# auxDaqUnit.net
KiCad netlist of a schematic drawn in EAGLE
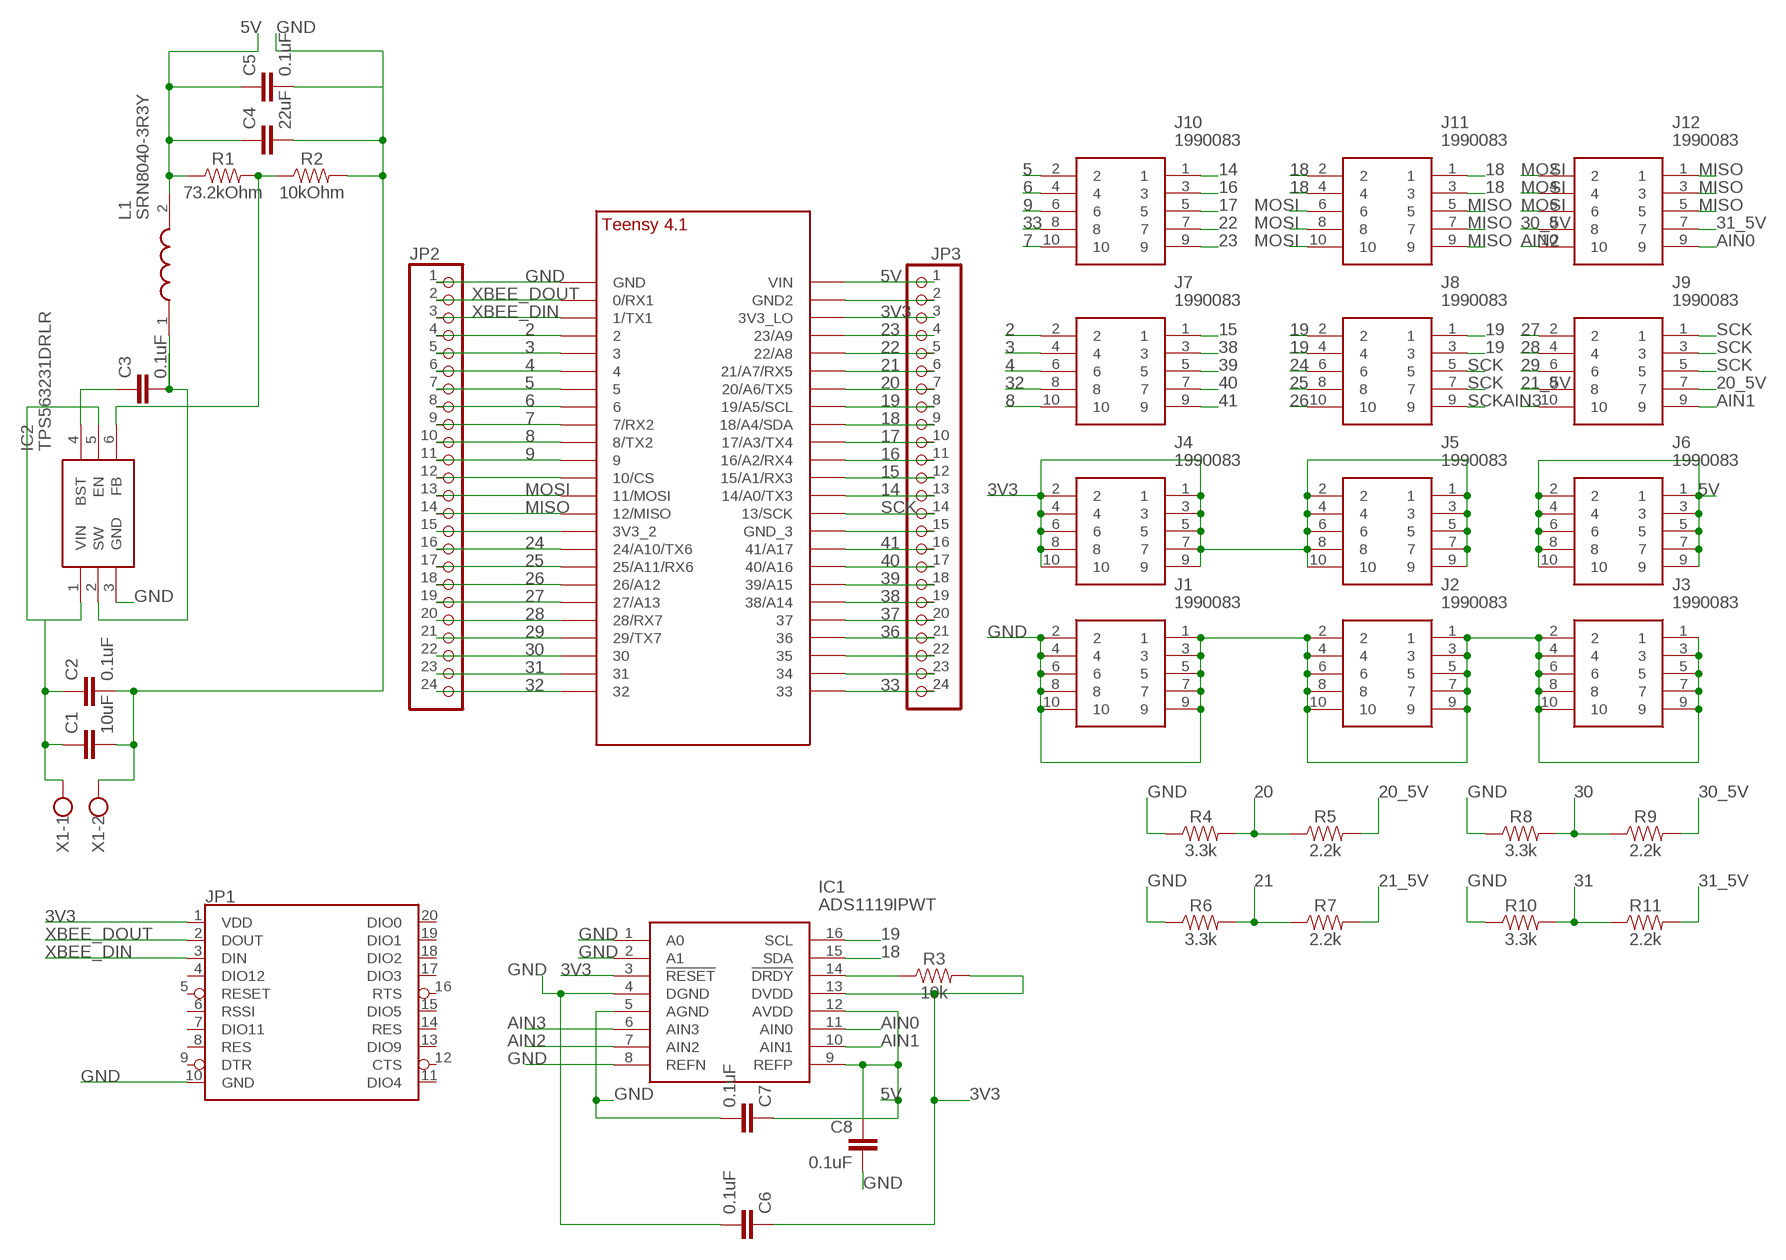
[diagram p0: schematic, sheet 1]

(export (version "E")
  (design (tool "Eeschema 10.0.6"))
  (components
    (comp (ref "C1")
      (value "10uF")
      (footprint "eagle-import:0603")
      (libsource (lib "eagle-import") (part "10UF-0603-6.3V-20%"))
    )
    (comp (ref "C2")
      (value "0.1uF")
      (footprint "eagle-import:0603")
      (libsource (lib "eagle-import") (part "0.1UF-0603-25V-(+80/-20%)"))
    )
    (comp (ref "C3")
      (value "0.1uF")
      (footprint "eagle-import:0603")
      (libsource (lib "eagle-import") (part "0.1UF-0603-25V-(+80/-20%)"))
    )
    (comp (ref "C4")
      (value "22uF")
      (footprint "eagle-import:0805")
      (libsource (lib "eagle-import") (part "22UF-0805-6.3V-20%"))
    )
    (comp (ref "C5")
      (value "0.1uF")
      (footprint "eagle-import:0603")
      (libsource (lib "eagle-import") (part "0.1UF-0603-25V-(+80/-20%)"))
    )
    (comp (ref "C6")
      (value "0.1uF")
      (footprint "eagle-import:0603")
      (libsource (lib "eagle-import") (part "0.1UF-0603-25V-(+80/-20%)"))
    )
    (comp (ref "C7")
      (value "0.1uF")
      (footprint "eagle-import:0603")
      (libsource (lib "eagle-import") (part "0.1UF-0603-25V-(+80/-20%)"))
    )
    (comp (ref "C8")
      (value "0.1uF")
      (footprint "eagle-import:0603")
      (libsource (lib "eagle-import") (part "0.1UF-0603-25V-(+80/-20%)"))
    )
    (comp (ref "IC1")
      (value "ADS1119IPWT")
      (footprint "eagle-import:SOP65P640X120-16N")
      (fields (field (name "MOUSER_PART_NUMBER") "595-ADS1119IPWT"))
      (libsource (lib "eagle-import") (part "ADS1119IPWT"))
    )
    (comp (ref "IC2")
      (value "TPS563231DRLR")
      (footprint "eagle-import:SOTFL50P160X60-6N")
      (fields (field (name "MOUSER_PART_NUMBER") "595-TPS563231DRLR"))
      (libsource (lib "eagle-import") (part "TPS563231DRLR"))
    )
    (comp (ref "J1")
      (value "1990083")
      (footprint "eagle-import:1990083")
      (fields (field (name "MOUSER_PART_NUMBER") "651-1990083"))
      (libsource (lib "eagle-import") (part "1990083"))
    )
    (comp (ref "J2")
      (value "1990083")
      (footprint "eagle-import:1990083")
      (fields (field (name "MOUSER_PART_NUMBER") "651-1990083"))
      (libsource (lib "eagle-import") (part "1990083"))
    )
    (comp (ref "J3")
      (value "1990083")
      (footprint "eagle-import:1990083")
      (fields (field (name "MOUSER_PART_NUMBER") "651-1990083"))
      (libsource (lib "eagle-import") (part "1990083"))
    )
    (comp (ref "J4")
      (value "1990083")
      (footprint "eagle-import:1990083")
      (fields (field (name "MOUSER_PART_NUMBER") "651-1990083"))
      (libsource (lib "eagle-import") (part "1990083"))
    )
    (comp (ref "J5")
      (value "1990083")
      (footprint "eagle-import:1990083")
      (fields (field (name "MOUSER_PART_NUMBER") "651-1990083"))
      (libsource (lib "eagle-import") (part "1990083"))
    )
    (comp (ref "J6")
      (value "1990083")
      (footprint "eagle-import:1990083")
      (fields (field (name "MOUSER_PART_NUMBER") "651-1990083"))
      (libsource (lib "eagle-import") (part "1990083"))
    )
    (comp (ref "J7")
      (value "1990083")
      (footprint "eagle-import:1990083")
      (fields (field (name "MOUSER_PART_NUMBER") "651-1990083"))
      (libsource (lib "eagle-import") (part "1990083"))
    )
    (comp (ref "J8")
      (value "1990083")
      (footprint "eagle-import:1990083")
      (fields (field (name "MOUSER_PART_NUMBER") "651-1990083"))
      (libsource (lib "eagle-import") (part "1990083"))
    )
    (comp (ref "J9")
      (value "1990083")
      (footprint "eagle-import:1990083")
      (fields (field (name "MOUSER_PART_NUMBER") "651-1990083"))
      (libsource (lib "eagle-import") (part "1990083"))
    )
    (comp (ref "J10")
      (value "1990083")
      (footprint "eagle-import:1990083")
      (fields (field (name "MOUSER_PART_NUMBER") "651-1990083"))
      (libsource (lib "eagle-import") (part "1990083"))
    )
    (comp (ref "J11")
      (value "1990083")
      (footprint "eagle-import:1990083")
      (fields (field (name "MOUSER_PART_NUMBER") "651-1990083"))
      (libsource (lib "eagle-import") (part "1990083"))
    )
    (comp (ref "J12")
      (value "1990083")
      (footprint "eagle-import:1990083")
      (fields (field (name "MOUSER_PART_NUMBER") "651-1990083"))
      (libsource (lib "eagle-import") (part "1990083"))
    )
    (comp (ref "JP1")
      (value "XBEE")
      (footprint "eagle-import:XBEE")
      (libsource (lib "eagle-import") (part "XBEE"))
    )
    (comp (ref "JP2")
      (value "PINHD-1X24")
      (footprint "eagle-import:1X24")
      (libsource (lib "eagle-import") (part "PINHD-1X24"))
    )
    (comp (ref "JP3")
      (value "PINHD-1X24")
      (footprint "eagle-import:1X24")
      (libsource (lib "eagle-import") (part "PINHD-1X24"))
    )
    (comp (ref "L1")
      (value "SRN8040-3R3Y")
      (footprint "eagle-import:SRN8040-3R3Y")
      (fields (field (name "MOUSER_PART_NUMBER") "652-SRN8040-3R3Y"))
      (libsource (lib "eagle-import") (part "SRN8040-3R3Y"))
    )
    (comp (ref "R1")
      (value "73.2kOhm")
      (footprint "eagle-import:0603")
      (libsource (lib "eagle-import") (part "RESISTOR0603"))
    )
    (comp (ref "R2")
      (value "10kOhm")
      (footprint "eagle-import:0603")
      (libsource (lib "eagle-import") (part "RESISTOR0603"))
    )
    (comp (ref "R3")
      (value "10k")
      (footprint "eagle-import:0603")
      (libsource (lib "eagle-import") (part "10KOHM-0603-1/10W-1%"))
    )
    (comp (ref "R4")
      (value "3.3k")
      (footprint "eagle-import:0603")
      (libsource (lib "eagle-import") (part "3.3KOHM-0603-1/10W-1%"))
    )
    (comp (ref "R5")
      (value "2.2k")
      (footprint "eagle-import:0603")
      (libsource (lib "eagle-import") (part "2.2KOHM-0603-1/10W-1%"))
    )
    (comp (ref "R6")
      (value "3.3k")
      (footprint "eagle-import:0603")
      (libsource (lib "eagle-import") (part "3.3KOHM-0603-1/10W-1%"))
    )
    (comp (ref "R7")
      (value "2.2k")
      (footprint "eagle-import:0603")
      (libsource (lib "eagle-import") (part "2.2KOHM-0603-1/10W-1%"))
    )
    (comp (ref "R8")
      (value "3.3k")
      (footprint "eagle-import:0603")
      (libsource (lib "eagle-import") (part "3.3KOHM-0603-1/10W-1%"))
    )
    (comp (ref "R9")
      (value "2.2k")
      (footprint "eagle-import:0603")
      (libsource (lib "eagle-import") (part "2.2KOHM-0603-1/10W-1%"))
    )
    (comp (ref "R10")
      (value "3.3k")
      (footprint "eagle-import:0603")
      (libsource (lib "eagle-import") (part "3.3KOHM-0603-1/10W-1%"))
    )
    (comp (ref "R11")
      (value "2.2k")
      (footprint "eagle-import:0603")
      (libsource (lib "eagle-import") (part "2.2KOHM-0603-1/10W-1%"))
    )
    (comp (ref "U$1")
      (value "TEENSY_4.1_SIMPLE")
      (footprint "eagle-import:TEENSY_4.1_SIMPLE")
      (libsource (lib "eagle-import") (part "TEENSY_4.1_SIMPLE"))
    )
    (comp (ref "X1")
      (value "W237-102")
      (footprint "eagle-import:W237-102")
      (fields (field (name "MPN") "237-102"))
      (libsource (lib "eagle-import") (part "W237-102"))
    )
  )
  (nets
    (net (code "1") (name "/2") (class "Default")
      (node (ref "J7") (pin "2") (pinfunction "2_2") (pintype "bidirectional"))
      (node (ref "JP2") (pin "4") (pinfunction "4_4") (pintype "passive"))
      (node (ref "U$1") (pin "2") (pinfunction "2_2") (pintype "bidirectional"))
    )
    (net (code "2") (name "/3") (class "Default")
      (node (ref "J7") (pin "4") (pinfunction "4_4") (pintype "bidirectional"))
      (node (ref "JP2") (pin "5") (pinfunction "5_5") (pintype "passive"))
      (node (ref "U$1") (pin "3/CANTX") (pinfunction "3_3/CANTX") (pintype "bidirectional"))
    )
    (net (code "3") (name "/3V3") (class "Default")
      (node (ref "C6") (pin "1") (pinfunction "1_1") (pintype "passive"))
      (node (ref "IC1") (pin "13") (pinfunction "DVDD_13") (pintype "bidirectional"))
      (node (ref "IC1") (pin "3") (pinfunction "~{RESET}_3") (pintype "bidirectional"))
      (node (ref "J4") (pin "1") (pinfunction "1_1") (pintype "bidirectional"))
      (node (ref "J4") (pin "10") (pinfunction "10_10") (pintype "bidirectional"))
      (node (ref "J4") (pin "2") (pinfunction "2_2") (pintype "bidirectional"))
      (node (ref "J4") (pin "3") (pinfunction "3_3") (pintype "bidirectional"))
      (node (ref "J4") (pin "4") (pinfunction "4_4") (pintype "bidirectional"))
      (node (ref "J4") (pin "5") (pinfunction "5_5") (pintype "bidirectional"))
      (node (ref "J4") (pin "6") (pinfunction "6_6") (pintype "bidirectional"))
      (node (ref "J4") (pin "7") (pinfunction "7_7") (pintype "bidirectional"))
      (node (ref "J4") (pin "8") (pinfunction "8_8") (pintype "bidirectional"))
      (node (ref "J4") (pin "9") (pinfunction "9_9") (pintype "bidirectional"))
      (node (ref "J5") (pin "1") (pinfunction "1_1") (pintype "bidirectional"))
      (node (ref "J5") (pin "10") (pinfunction "10_10") (pintype "bidirectional"))
      (node (ref "J5") (pin "2") (pinfunction "2_2") (pintype "bidirectional"))
      (node (ref "J5") (pin "3") (pinfunction "3_3") (pintype "bidirectional"))
      (node (ref "J5") (pin "4") (pinfunction "4_4") (pintype "bidirectional"))
      (node (ref "J5") (pin "5") (pinfunction "5_5") (pintype "bidirectional"))
      (node (ref "J5") (pin "6") (pinfunction "6_6") (pintype "bidirectional"))
      (node (ref "J5") (pin "7") (pinfunction "7_7") (pintype "bidirectional"))
      (node (ref "J5") (pin "8") (pinfunction "8_8") (pintype "bidirectional"))
      (node (ref "J5") (pin "9") (pinfunction "9_9") (pintype "bidirectional"))
      (node (ref "JP1") (pin "1") (pinfunction "VDD_1") (pintype "power_in"))
      (node (ref "JP3") (pin "3") (pinfunction "3_3") (pintype "passive"))
      (node (ref "R3") (pin "2") (pinfunction "2_2") (pintype "passive"))
      (node (ref "U$1") (pin "3V3_LO") (pinfunction "3V3_LO_3V3_LO") (pintype "bidirectional"))
    )
    (net (code "4") (name "/4") (class "Default")
      (node (ref "J7") (pin "6") (pinfunction "6_6") (pintype "bidirectional"))
      (node (ref "JP2") (pin "6") (pinfunction "6_6") (pintype "passive"))
      (node (ref "U$1") (pin "4/CANRX") (pinfunction "4_4/CANRX") (pintype "bidirectional"))
    )
    (net (code "5") (name "/5") (class "Default")
      (node (ref "J10") (pin "2") (pinfunction "2_2") (pintype "bidirectional"))
      (node (ref "JP2") (pin "7") (pinfunction "7_7") (pintype "passive"))
      (node (ref "U$1") (pin "5") (pinfunction "5_5") (pintype "bidirectional"))
    )
    (net (code "6") (name "/5V") (class "Default")
      (node (ref "C4") (pin "1") (pinfunction "1_1") (pintype "passive"))
      (node (ref "C5") (pin "1") (pinfunction "1_1") (pintype "passive"))
      (node (ref "C7") (pin "1") (pinfunction "1_1") (pintype "passive"))
      (node (ref "C8") (pin "1") (pinfunction "1_1") (pintype "passive"))
      (node (ref "IC1") (pin "12") (pinfunction "AVDD_12") (pintype "bidirectional"))
      (node (ref "IC1") (pin "9") (pinfunction "REFP_9") (pintype "bidirectional"))
      (node (ref "J6") (pin "1") (pinfunction "1_1") (pintype "bidirectional"))
      (node (ref "J6") (pin "10") (pinfunction "10_10") (pintype "bidirectional"))
      (node (ref "J6") (pin "2") (pinfunction "2_2") (pintype "bidirectional"))
      (node (ref "J6") (pin "3") (pinfunction "3_3") (pintype "bidirectional"))
      (node (ref "J6") (pin "4") (pinfunction "4_4") (pintype "bidirectional"))
      (node (ref "J6") (pin "5") (pinfunction "5_5") (pintype "bidirectional"))
      (node (ref "J6") (pin "6") (pinfunction "6_6") (pintype "bidirectional"))
      (node (ref "J6") (pin "7") (pinfunction "7_7") (pintype "bidirectional"))
      (node (ref "J6") (pin "8") (pinfunction "8_8") (pintype "bidirectional"))
      (node (ref "J6") (pin "9") (pinfunction "9_9") (pintype "bidirectional"))
      (node (ref "JP3") (pin "1") (pinfunction "1_1") (pintype "passive"))
      (node (ref "L1") (pin "2") (pinfunction "2_2") (pintype "bidirectional"))
      (node (ref "R1") (pin "1") (pinfunction "1_1") (pintype "passive"))
      (node (ref "U$1") (pin "VIN") (pinfunction "VIN_VIN") (pintype "bidirectional"))
    )
    (net (code "7") (name "/6") (class "Default")
      (node (ref "J10") (pin "4") (pinfunction "4_4") (pintype "bidirectional"))
      (node (ref "JP2") (pin "8") (pinfunction "8_8") (pintype "passive"))
      (node (ref "U$1") (pin "6") (pinfunction "6_6") (pintype "bidirectional"))
    )
    (net (code "8") (name "/7") (class "Default")
      (node (ref "J10") (pin "10") (pinfunction "10_10") (pintype "bidirectional"))
      (node (ref "JP2") (pin "9") (pinfunction "9_9") (pintype "passive"))
      (node (ref "U$1") (pin "7") (pinfunction "7/RX2_7") (pintype "bidirectional"))
    )
    (net (code "9") (name "/8") (class "Default")
      (node (ref "J7") (pin "10") (pinfunction "10_10") (pintype "bidirectional"))
      (node (ref "JP2") (pin "10") (pinfunction "10_10") (pintype "passive"))
      (node (ref "U$1") (pin "8") (pinfunction "8/TX2_8") (pintype "bidirectional"))
    )
    (net (code "10") (name "/9") (class "Default")
      (node (ref "J10") (pin "6") (pinfunction "6_6") (pintype "bidirectional"))
      (node (ref "JP2") (pin "11") (pinfunction "11_11") (pintype "passive"))
      (node (ref "U$1") (pin "9/CS") (pinfunction "9_9/CS") (pintype "bidirectional"))
    )
    (net (code "11") (name "/14") (class "Default")
      (node (ref "J10") (pin "1") (pinfunction "1_1") (pintype "bidirectional"))
      (node (ref "JP3") (pin "13") (pinfunction "13_13") (pintype "passive"))
      (node (ref "U$1") (pin "14/A0") (pinfunction "14/A0/TX3_14/A0") (pintype "bidirectional"))
    )
    (net (code "12") (name "/15") (class "Default")
      (node (ref "J7") (pin "1") (pinfunction "1_1") (pintype "bidirectional"))
      (node (ref "JP3") (pin "12") (pinfunction "12_12") (pintype "passive"))
      (node (ref "U$1") (pin "15/A1") (pinfunction "15/A1/RX3_15/A1") (pintype "bidirectional"))
    )
    (net (code "13") (name "/16") (class "Default")
      (node (ref "J10") (pin "3") (pinfunction "3_3") (pintype "bidirectional"))
      (node (ref "JP3") (pin "11") (pinfunction "11_11") (pintype "passive"))
      (node (ref "U$1") (pin "16/A2") (pinfunction "16/A2/RX4_16/A2") (pintype "bidirectional"))
    )
    (net (code "14") (name "/17") (class "Default")
      (node (ref "J10") (pin "5") (pinfunction "5_5") (pintype "bidirectional"))
      (node (ref "JP3") (pin "10") (pinfunction "10_10") (pintype "passive"))
      (node (ref "U$1") (pin "17/A3") (pinfunction "17/A3/TX4_17/A3") (pintype "bidirectional"))
    )
    (net (code "15") (name "/18") (class "Default")
      (node (ref "IC1") (pin "15") (pinfunction "SDA_15") (pintype "bidirectional"))
      (node (ref "J11") (pin "1") (pinfunction "1_1") (pintype "bidirectional"))
      (node (ref "J11") (pin "2") (pinfunction "2_2") (pintype "bidirectional"))
      (node (ref "J11") (pin "3") (pinfunction "3_3") (pintype "bidirectional"))
      (node (ref "J11") (pin "4") (pinfunction "4_4") (pintype "bidirectional"))
      (node (ref "JP3") (pin "9") (pinfunction "9_9") (pintype "passive"))
      (node (ref "U$1") (pin "18/A4/SDA") (pinfunction "18/A4/SDA_18/A4/SDA") (pintype "bidirectional"))
    )
    (net (code "16") (name "/19") (class "Default")
      (node (ref "IC1") (pin "16") (pinfunction "SCL_16") (pintype "bidirectional"))
      (node (ref "J8") (pin "1") (pinfunction "1_1") (pintype "bidirectional"))
      (node (ref "J8") (pin "2") (pinfunction "2_2") (pintype "bidirectional"))
      (node (ref "J8") (pin "3") (pinfunction "3_3") (pintype "bidirectional"))
      (node (ref "J8") (pin "4") (pinfunction "4_4") (pintype "bidirectional"))
      (node (ref "JP3") (pin "8") (pinfunction "8_8") (pintype "passive"))
      (node (ref "U$1") (pin "19/A5/SCL") (pinfunction "19/A5/SCL_19/A5/SCL") (pintype "bidirectional"))
    )
    (net (code "17") (name "/20") (class "Default")
      (node (ref "JP3") (pin "7") (pinfunction "7_7") (pintype "passive"))
      (node (ref "R4") (pin "2") (pinfunction "2_2") (pintype "passive"))
      (node (ref "R5") (pin "1") (pinfunction "1_1") (pintype "passive"))
      (node (ref "U$1") (pin "20/A6") (pinfunction "20/A6/TX5_20/A6") (pintype "bidirectional"))
    )
    (net (code "18") (name "/20_5V") (class "Default")
      (node (ref "J9") (pin "7") (pinfunction "7_7") (pintype "bidirectional"))
      (node (ref "R5") (pin "2") (pinfunction "2_2") (pintype "passive"))
    )
    (net (code "19") (name "/21") (class "Default")
      (node (ref "JP3") (pin "6") (pinfunction "6_6") (pintype "passive"))
      (node (ref "R6") (pin "2") (pinfunction "2_2") (pintype "passive"))
      (node (ref "R7") (pin "1") (pinfunction "1_1") (pintype "passive"))
      (node (ref "U$1") (pin "21/A7") (pinfunction "21/A7/RX5_21/A7") (pintype "bidirectional"))
    )
    (net (code "20") (name "/21_5V") (class "Default")
      (node (ref "J9") (pin "8") (pinfunction "8_8") (pintype "bidirectional"))
      (node (ref "R7") (pin "2") (pinfunction "2_2") (pintype "passive"))
    )
    (net (code "21") (name "/22") (class "Default")
      (node (ref "J10") (pin "7") (pinfunction "7_7") (pintype "bidirectional"))
      (node (ref "JP3") (pin "5") (pinfunction "5_5") (pintype "passive"))
      (node (ref "U$1") (pin "22/A8") (pinfunction "22/A8_22/A8") (pintype "bidirectional"))
    )
    (net (code "22") (name "/23") (class "Default")
      (node (ref "J10") (pin "9") (pinfunction "9_9") (pintype "bidirectional"))
      (node (ref "JP3") (pin "4") (pinfunction "4_4") (pintype "passive"))
      (node (ref "U$1") (pin "23/A9") (pinfunction "23/A9_23/A9") (pintype "bidirectional"))
    )
    (net (code "23") (name "/24") (class "Default")
      (node (ref "J8") (pin "6") (pinfunction "6_6") (pintype "bidirectional"))
      (node (ref "JP2") (pin "16") (pinfunction "16_16") (pintype "passive"))
      (node (ref "U$1") (pin "24/A10") (pinfunction "24/A10/TX6_24/A10") (pintype "bidirectional"))
    )
    (net (code "24") (name "/25") (class "Default")
      (node (ref "J8") (pin "8") (pinfunction "8_8") (pintype "bidirectional"))
      (node (ref "JP2") (pin "17") (pinfunction "17_17") (pintype "passive"))
      (node (ref "U$1") (pin "25/A11") (pinfunction "25/A11/RX6_25/A11") (pintype "bidirectional"))
    )
    (net (code "25") (name "/26") (class "Default")
      (node (ref "J8") (pin "10") (pinfunction "10_10") (pintype "bidirectional"))
      (node (ref "JP2") (pin "18") (pinfunction "18_18") (pintype "passive"))
      (node (ref "U$1") (pin "26/A12") (pinfunction "26/A12_26/A12") (pintype "bidirectional"))
    )
    (net (code "26") (name "/27") (class "Default")
      (node (ref "J9") (pin "2") (pinfunction "2_2") (pintype "bidirectional"))
      (node (ref "JP2") (pin "19") (pinfunction "19_19") (pintype "passive"))
      (node (ref "U$1") (pin "27/A13") (pinfunction "27/A13_27/A13") (pintype "bidirectional"))
    )
    (net (code "27") (name "/28") (class "Default")
      (node (ref "J9") (pin "4") (pinfunction "4_4") (pintype "bidirectional"))
      (node (ref "JP2") (pin "20") (pinfunction "20_20") (pintype "passive"))
      (node (ref "U$1") (pin "28") (pinfunction "28/RX7_28") (pintype "bidirectional"))
    )
    (net (code "28") (name "/29") (class "Default")
      (node (ref "J9") (pin "6") (pinfunction "6_6") (pintype "bidirectional"))
      (node (ref "JP2") (pin "21") (pinfunction "21_21") (pintype "passive"))
      (node (ref "U$1") (pin "29") (pinfunction "29/TX7_29") (pintype "bidirectional"))
    )
    (net (code "29") (name "/30") (class "Default")
      (node (ref "JP2") (pin "22") (pinfunction "22_22") (pintype "passive"))
      (node (ref "R8") (pin "2") (pinfunction "2_2") (pintype "passive"))
      (node (ref "R9") (pin "1") (pinfunction "1_1") (pintype "passive"))
      (node (ref "U$1") (pin "30") (pinfunction "30_30") (pintype "bidirectional"))
    )
    (net (code "30") (name "/30_5V") (class "Default")
      (node (ref "J12") (pin "8") (pinfunction "8_8") (pintype "bidirectional"))
      (node (ref "R9") (pin "2") (pinfunction "2_2") (pintype "passive"))
    )
    (net (code "31") (name "/31") (class "Default")
      (node (ref "JP2") (pin "23") (pinfunction "23_23") (pintype "passive"))
      (node (ref "R10") (pin "2") (pinfunction "2_2") (pintype "passive"))
      (node (ref "R11") (pin "1") (pinfunction "1_1") (pintype "passive"))
      (node (ref "U$1") (pin "31") (pinfunction "31_31") (pintype "bidirectional"))
    )
    (net (code "32") (name "/31_5V") (class "Default")
      (node (ref "J12") (pin "7") (pinfunction "7_7") (pintype "bidirectional"))
      (node (ref "R11") (pin "2") (pinfunction "2_2") (pintype "passive"))
    )
    (net (code "33") (name "/32") (class "Default")
      (node (ref "J7") (pin "8") (pinfunction "8_8") (pintype "bidirectional"))
      (node (ref "JP2") (pin "24") (pinfunction "24_24") (pintype "passive"))
      (node (ref "U$1") (pin "32") (pinfunction "32_32") (pintype "bidirectional"))
    )
    (net (code "34") (name "/33") (class "Default")
      (node (ref "J10") (pin "8") (pinfunction "8_8") (pintype "bidirectional"))
      (node (ref "JP3") (pin "24") (pinfunction "24_24") (pintype "passive"))
      (node (ref "U$1") (pin "33") (pinfunction "33_33") (pintype "bidirectional"))
    )
    (net (code "35") (name "/36") (class "Default")
      (node (ref "JP3") (pin "21") (pinfunction "21_21") (pintype "passive"))
      (node (ref "U$1") (pin "36") (pinfunction "36_36") (pintype "bidirectional"))
    )
    (net (code "36") (name "/37") (class "Default")
      (node (ref "JP3") (pin "20") (pinfunction "20_20") (pintype "passive"))
      (node (ref "U$1") (pin "37") (pinfunction "37_37") (pintype "bidirectional"))
    )
    (net (code "37") (name "/38") (class "Default")
      (node (ref "J7") (pin "3") (pinfunction "3_3") (pintype "bidirectional"))
      (node (ref "JP3") (pin "19") (pinfunction "19_19") (pintype "passive"))
      (node (ref "U$1") (pin "38/A14") (pinfunction "38/A14_38/A14") (pintype "bidirectional"))
    )
    (net (code "38") (name "/39") (class "Default")
      (node (ref "J7") (pin "5") (pinfunction "5_5") (pintype "bidirectional"))
      (node (ref "JP3") (pin "18") (pinfunction "18_18") (pintype "passive"))
      (node (ref "U$1") (pin "39/A15") (pinfunction "39/A15_39/A15") (pintype "bidirectional"))
    )
    (net (code "39") (name "/40") (class "Default")
      (node (ref "J7") (pin "7") (pinfunction "7_7") (pintype "bidirectional"))
      (node (ref "JP3") (pin "17") (pinfunction "17_17") (pintype "passive"))
      (node (ref "U$1") (pin "40/A16") (pinfunction "40/A16_40/A16") (pintype "bidirectional"))
    )
    (net (code "40") (name "/41") (class "Default")
      (node (ref "J7") (pin "9") (pinfunction "9_9") (pintype "bidirectional"))
      (node (ref "JP3") (pin "16") (pinfunction "16_16") (pintype "passive"))
      (node (ref "U$1") (pin "41/A17") (pinfunction "41/A17_41/A17") (pintype "bidirectional"))
    )
    (net (code "41") (name "/AIN0") (class "Default")
      (node (ref "IC1") (pin "11") (pinfunction "AIN0_11") (pintype "bidirectional"))
      (node (ref "J12") (pin "9") (pinfunction "9_9") (pintype "bidirectional"))
    )
    (net (code "42") (name "/AIN1") (class "Default")
      (node (ref "IC1") (pin "10") (pinfunction "AIN1_10") (pintype "bidirectional"))
      (node (ref "J9") (pin "9") (pinfunction "9_9") (pintype "bidirectional"))
    )
    (net (code "43") (name "/AIN2") (class "Default")
      (node (ref "IC1") (pin "7") (pinfunction "AIN2_7") (pintype "bidirectional"))
      (node (ref "J12") (pin "10") (pinfunction "10_10") (pintype "bidirectional"))
    )
    (net (code "44") (name "/AIN3") (class "Default")
      (node (ref "IC1") (pin "6") (pinfunction "AIN3_6") (pintype "bidirectional"))
      (node (ref "J9") (pin "10") (pinfunction "10_10") (pintype "bidirectional"))
    )
    (net (code "45") (name "/GND") (class "Default")
      (node (ref "C1") (pin "2") (pinfunction "2_2") (pintype "passive"))
      (node (ref "C2") (pin "2") (pinfunction "2_2") (pintype "passive"))
      (node (ref "C4") (pin "2") (pinfunction "2_2") (pintype "passive"))
      (node (ref "C5") (pin "2") (pinfunction "2_2") (pintype "passive"))
      (node (ref "C6") (pin "2") (pinfunction "2_2") (pintype "passive"))
      (node (ref "C7") (pin "2") (pinfunction "2_2") (pintype "passive"))
      (node (ref "C8") (pin "2") (pinfunction "2_2") (pintype "passive"))
      (node (ref "IC1") (pin "1") (pinfunction "A0_1") (pintype "bidirectional"))
      (node (ref "IC1") (pin "2") (pinfunction "A1_2") (pintype "bidirectional"))
      (node (ref "IC1") (pin "4") (pinfunction "DGND_4") (pintype "bidirectional"))
      (node (ref "IC1") (pin "5") (pinfunction "AGND_5") (pintype "bidirectional"))
      (node (ref "IC1") (pin "8") (pinfunction "REFN_8") (pintype "bidirectional"))
      (node (ref "IC2") (pin "3") (pinfunction "GND_3") (pintype "bidirectional"))
      (node (ref "J1") (pin "1") (pinfunction "1_1") (pintype "bidirectional"))
      (node (ref "J1") (pin "10") (pinfunction "10_10") (pintype "bidirectional"))
      (node (ref "J1") (pin "2") (pinfunction "2_2") (pintype "bidirectional"))
      (node (ref "J1") (pin "3") (pinfunction "3_3") (pintype "bidirectional"))
      (node (ref "J1") (pin "4") (pinfunction "4_4") (pintype "bidirectional"))
      (node (ref "J1") (pin "5") (pinfunction "5_5") (pintype "bidirectional"))
      (node (ref "J1") (pin "6") (pinfunction "6_6") (pintype "bidirectional"))
      (node (ref "J1") (pin "7") (pinfunction "7_7") (pintype "bidirectional"))
      (node (ref "J1") (pin "8") (pinfunction "8_8") (pintype "bidirectional"))
      (node (ref "J1") (pin "9") (pinfunction "9_9") (pintype "bidirectional"))
      (node (ref "J2") (pin "1") (pinfunction "1_1") (pintype "bidirectional"))
      (node (ref "J2") (pin "10") (pinfunction "10_10") (pintype "bidirectional"))
      (node (ref "J2") (pin "2") (pinfunction "2_2") (pintype "bidirectional"))
      (node (ref "J2") (pin "3") (pinfunction "3_3") (pintype "bidirectional"))
      (node (ref "J2") (pin "4") (pinfunction "4_4") (pintype "bidirectional"))
      (node (ref "J2") (pin "5") (pinfunction "5_5") (pintype "bidirectional"))
      (node (ref "J2") (pin "6") (pinfunction "6_6") (pintype "bidirectional"))
      (node (ref "J2") (pin "7") (pinfunction "7_7") (pintype "bidirectional"))
      (node (ref "J2") (pin "8") (pinfunction "8_8") (pintype "bidirectional"))
      (node (ref "J2") (pin "9") (pinfunction "9_9") (pintype "bidirectional"))
      (node (ref "J3") (pin "1") (pinfunction "1_1") (pintype "bidirectional"))
      (node (ref "J3") (pin "10") (pinfunction "10_10") (pintype "bidirectional"))
      (node (ref "J3") (pin "2") (pinfunction "2_2") (pintype "bidirectional"))
      (node (ref "J3") (pin "3") (pinfunction "3_3") (pintype "bidirectional"))
      (node (ref "J3") (pin "4") (pinfunction "4_4") (pintype "bidirectional"))
      (node (ref "J3") (pin "5") (pinfunction "5_5") (pintype "bidirectional"))
      (node (ref "J3") (pin "6") (pinfunction "6_6") (pintype "bidirectional"))
      (node (ref "J3") (pin "7") (pinfunction "7_7") (pintype "bidirectional"))
      (node (ref "J3") (pin "8") (pinfunction "8_8") (pintype "bidirectional"))
      (node (ref "J3") (pin "9") (pinfunction "9_9") (pintype "bidirectional"))
      (node (ref "JP1") (pin "10") (pinfunction "GND_10") (pintype "power_in"))
      (node (ref "JP2") (pin "1") (pinfunction "1_1") (pintype "passive"))
      (node (ref "R10") (pin "1") (pinfunction "1_1") (pintype "passive"))
      (node (ref "R2") (pin "2") (pinfunction "2_2") (pintype "passive"))
      (node (ref "R4") (pin "1") (pinfunction "1_1") (pintype "passive"))
      (node (ref "R6") (pin "1") (pinfunction "1_1") (pintype "passive"))
      (node (ref "R8") (pin "1") (pinfunction "1_1") (pintype "passive"))
      (node (ref "U$1") (pin "GND") (pinfunction "GND_GND") (pintype "bidirectional"))
      (node (ref "X1") (pin "2") (pinfunction "KL_2") (pintype "passive"))
    )
    (net (code "46") (name "/MISO") (class "Default")
      (node (ref "J11") (pin "5") (pinfunction "5_5") (pintype "bidirectional"))
      (node (ref "J11") (pin "7") (pinfunction "7_7") (pintype "bidirectional"))
      (node (ref "J11") (pin "9") (pinfunction "9_9") (pintype "bidirectional"))
      (node (ref "J12") (pin "1") (pinfunction "1_1") (pintype "bidirectional"))
      (node (ref "J12") (pin "3") (pinfunction "3_3") (pintype "bidirectional"))
      (node (ref "J12") (pin "5") (pinfunction "5_5") (pintype "bidirectional"))
      (node (ref "JP2") (pin "14") (pinfunction "14_14") (pintype "passive"))
      (node (ref "U$1") (pin "12/MISO") (pinfunction "12/MISO_12/MISO") (pintype "bidirectional"))
    )
    (net (code "47") (name "/MOSI") (class "Default")
      (node (ref "J11") (pin "10") (pinfunction "10_10") (pintype "bidirectional"))
      (node (ref "J11") (pin "6") (pinfunction "6_6") (pintype "bidirectional"))
      (node (ref "J11") (pin "8") (pinfunction "8_8") (pintype "bidirectional"))
      (node (ref "J12") (pin "2") (pinfunction "2_2") (pintype "bidirectional"))
      (node (ref "J12") (pin "4") (pinfunction "4_4") (pintype "bidirectional"))
      (node (ref "J12") (pin "6") (pinfunction "6_6") (pintype "bidirectional"))
      (node (ref "JP2") (pin "13") (pinfunction "13_13") (pintype "passive"))
      (node (ref "U$1") (pin "11/MOSI") (pinfunction "11/MOSI_11/MOSI") (pintype "bidirectional"))
    )
    (net (code "48") (name "/SCK") (class "Default")
      (node (ref "J8") (pin "5") (pinfunction "5_5") (pintype "bidirectional"))
      (node (ref "J8") (pin "7") (pinfunction "7_7") (pintype "bidirectional"))
      (node (ref "J8") (pin "9") (pinfunction "9_9") (pintype "bidirectional"))
      (node (ref "J9") (pin "1") (pinfunction "1_1") (pintype "bidirectional"))
      (node (ref "J9") (pin "3") (pinfunction "3_3") (pintype "bidirectional"))
      (node (ref "J9") (pin "5") (pinfunction "5_5") (pintype "bidirectional"))
      (node (ref "JP3") (pin "14") (pinfunction "14_14") (pintype "passive"))
      (node (ref "U$1") (pin "13/SCK") (pinfunction "13/SCK_13/SCK") (pintype "bidirectional"))
    )
    (net (code "49") (name "/XBEE_DIN") (class "Default")
      (node (ref "JP1") (pin "3") (pinfunction "DIN_3") (pintype "input"))
      (node (ref "JP2") (pin "3") (pinfunction "3_3") (pintype "passive"))
      (node (ref "U$1") (pin "1/TX") (pinfunction "1/TX1_1/TX") (pintype "bidirectional"))
    )
    (net (code "50") (name "/XBEE_DOUT") (class "Default")
      (node (ref "JP1") (pin "2") (pinfunction "DOUT_2") (pintype "output"))
      (node (ref "JP2") (pin "2") (pinfunction "2_2") (pintype "passive"))
      (node (ref "U$1") (pin "0/RX") (pinfunction "0/RX1_0/RX") (pintype "bidirectional"))
    )
    (net (code "51") (name "Net-(IC1-~{DRDY})") (class "Default")
      (node (ref "IC1") (pin "14") (pinfunction "~{DRDY}_14") (pintype "bidirectional"))
      (node (ref "R3") (pin "1") (pinfunction "1_1") (pintype "passive"))
    )
    (net (code "52") (name "Net-(IC2-BST)") (class "Default")
      (node (ref "C3") (pin "1") (pinfunction "1_1") (pintype "passive"))
      (node (ref "IC2") (pin "4") (pinfunction "BST_4") (pintype "bidirectional"))
    )
    (net (code "53") (name "Net-(IC2-EN)") (class "Default")
      (node (ref "C1") (pin "1") (pinfunction "1_1") (pintype "passive"))
      (node (ref "C2") (pin "1") (pinfunction "1_1") (pintype "passive"))
      (node (ref "IC2") (pin "1") (pinfunction "VIN_1") (pintype "bidirectional"))
      (node (ref "IC2") (pin "5") (pinfunction "EN_5") (pintype "bidirectional"))
      (node (ref "X1") (pin "1") (pinfunction "KL_1") (pintype "passive"))
    )
    (net (code "54") (name "Net-(IC2-FB)") (class "Default")
      (node (ref "IC2") (pin "6") (pinfunction "FB_6") (pintype "bidirectional"))
      (node (ref "R1") (pin "2") (pinfunction "2_2") (pintype "passive"))
      (node (ref "R2") (pin "1") (pinfunction "1_1") (pintype "passive"))
    )
    (net (code "55") (name "Net-(IC2-SW)") (class "Default")
      (node (ref "C3") (pin "2") (pinfunction "2_2") (pintype "passive"))
      (node (ref "IC2") (pin "2") (pinfunction "SW_2") (pintype "bidirectional"))
      (node (ref "L1") (pin "1") (pinfunction "1_1") (pintype "bidirectional"))
    )
    (net (code "56") (name "Net-(JP2-Pad12)") (class "Default")
      (node (ref "JP2") (pin "12") (pinfunction "12_12") (pintype "passive"))
      (node (ref "U$1") (pin "10/CS") (pinfunction "10/CS_10/CS") (pintype "bidirectional"))
    )
    (net (code "57") (name "Net-(JP2-Pad15)") (class "Default")
      (node (ref "JP2") (pin "15") (pinfunction "15_15") (pintype "passive"))
      (node (ref "U$1") (pin "3V3_2") (pinfunction "3V3_2_3V3_2") (pintype "bidirectional"))
    )
    (net (code "58") (name "Net-(JP3-Pad2)") (class "Default")
      (node (ref "JP3") (pin "2") (pinfunction "2_2") (pintype "passive"))
      (node (ref "U$1") (pin "GND2") (pinfunction "GND2_GND2") (pintype "bidirectional"))
    )
    (net (code "59") (name "Net-(JP3-Pad22)") (class "Default")
      (node (ref "JP3") (pin "22") (pinfunction "22_22") (pintype "passive"))
      (node (ref "U$1") (pin "35") (pinfunction "35_35") (pintype "bidirectional"))
    )
    (net (code "60") (name "Net-(JP3-Pad23)") (class "Default")
      (node (ref "JP3") (pin "23") (pinfunction "23_23") (pintype "passive"))
      (node (ref "U$1") (pin "34") (pinfunction "34_34") (pintype "bidirectional"))
    )
    (net (code "61") (name "Net-(U$1-GND_3)") (class "Default")
      (node (ref "JP3") (pin "15") (pinfunction "15_15") (pintype "passive"))
      (node (ref "U$1") (pin "GND3") (pinfunction "GND_3_GND3") (pintype "bidirectional"))
    )
    (net (code "62") (name "unconnected-(JP1-CTS-Pad12)") (class "Default")
      (node (ref "JP1") (pin "12") (pinfunction "CTS_12") (pintype "output"))
    )
    (net (code "63") (name "unconnected-(JP1-DIO0-Pad20)") (class "Default")
      (node (ref "JP1") (pin "20") (pinfunction "DIO0_20") (pintype "bidirectional"))
    )
    (net (code "64") (name "unconnected-(JP1-DIO1-Pad19)") (class "Default")
      (node (ref "JP1") (pin "19") (pinfunction "DIO1_19") (pintype "bidirectional"))
    )
    (net (code "65") (name "unconnected-(JP1-DIO2-Pad18)") (class "Default")
      (node (ref "JP1") (pin "18") (pinfunction "DIO2_18") (pintype "bidirectional"))
    )
    (net (code "66") (name "unconnected-(JP1-DIO3-Pad17)") (class "Default")
      (node (ref "JP1") (pin "17") (pinfunction "DIO3_17") (pintype "bidirectional"))
    )
    (net (code "67") (name "unconnected-(JP1-DIO4-Pad11)") (class "Default")
      (node (ref "JP1") (pin "11") (pinfunction "DIO4_11") (pintype "bidirectional"))
    )
    (net (code "68") (name "unconnected-(JP1-DIO5-Pad15)") (class "Default")
      (node (ref "JP1") (pin "15") (pinfunction "DIO5_15") (pintype "bidirectional"))
    )
    (net (code "69") (name "unconnected-(JP1-DIO9-Pad13)") (class "Default")
      (node (ref "JP1") (pin "13") (pinfunction "DIO9_13") (pintype "bidirectional"))
    )
    (net (code "70") (name "unconnected-(JP1-DIO11-Pad7)") (class "Default")
      (node (ref "JP1") (pin "7") (pinfunction "DIO11_7") (pintype "bidirectional"))
    )
    (net (code "71") (name "unconnected-(JP1-DIO12-Pad4)") (class "Default")
      (node (ref "JP1") (pin "4") (pinfunction "DIO12_4") (pintype "bidirectional"))
    )
    (net (code "72") (name "unconnected-(JP1-DTR-Pad9)") (class "Default")
      (node (ref "JP1") (pin "9") (pinfunction "DTR_9") (pintype "bidirectional"))
    )
    (net (code "73") (name "unconnected-(JP1-RES-Pad8)") (class "Default")
      (node (ref "JP1") (pin "8") (pinfunction "RES_8") (pintype "bidirectional"))
    )
    (net (code "74") (name "unconnected-(JP1-RES-Pad14)") (class "Default")
      (node (ref "JP1") (pin "14") (pinfunction "RES_14") (pintype "bidirectional"))
    )
    (net (code "75") (name "unconnected-(JP1-RESET-Pad5)") (class "Default")
      (node (ref "JP1") (pin "5") (pinfunction "RESET_5") (pintype "input"))
    )
    (net (code "76") (name "unconnected-(JP1-RSSI-Pad6)") (class "Default")
      (node (ref "JP1") (pin "6") (pinfunction "RSSI_6") (pintype "bidirectional"))
    )
    (net (code "77") (name "unconnected-(JP1-RTS-Pad16)") (class "Default")
      (node (ref "JP1") (pin "16") (pinfunction "RTS_16") (pintype "input"))
    )
  )
)
